# Motor_Control.net
KiCad netlist of a schematic drawn in Altium Designer
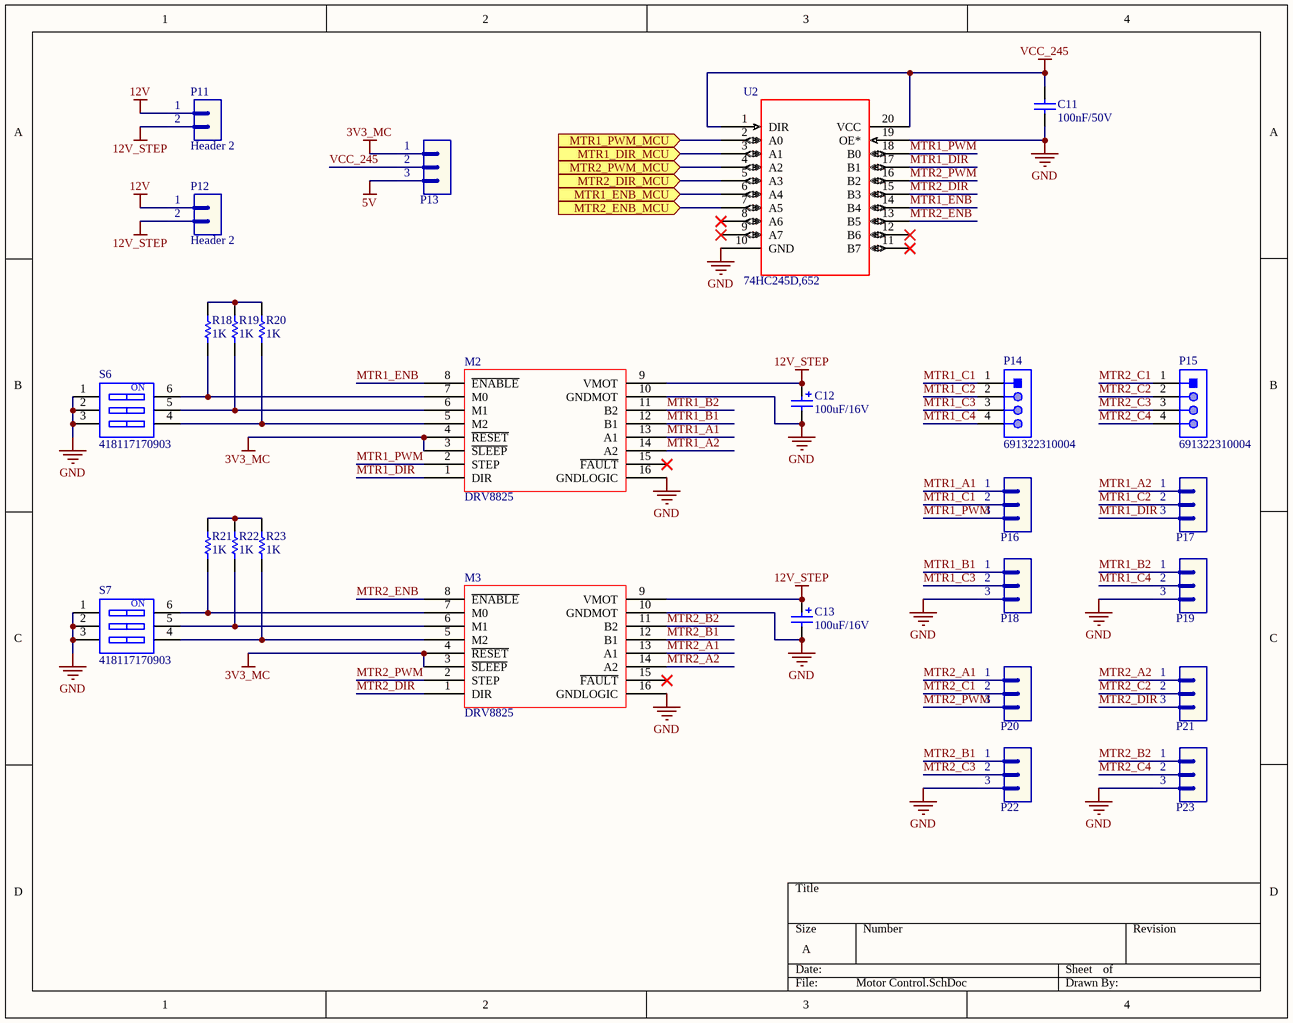
[diagram p0: Motor Control.SchDoc]

(export (version "E")
  (design (tool "Eeschema 10.0.6"))
  (components
    (comp (ref "C11")
      (value "100nF/50V")
      (footprint "CAP-SM-0805")
      (description "CAP CER 0.1UF 50V Y5V 0805")
      (fields
        (field (name "MANUFACTURER") "Samsung Electro-Mechanics")
        (field (name "MANUFACTURER PART NUMBER") "CL21F104ZBCNNNC")
      )
      (libsource (lib "Capacitor") (part "Cap-100nF-50V-0805"))
    )
    (comp (ref "C12")
      (value "100uF/16V")
      (footprint "CAP-SM-AL-SIZE-D-D6L6")
      (description "CAP ALUM 100UF 20% 16V SMD")
      (fields
        (field (name "MANUFACTURER") "Nichicon")
        (field (name "MANUFACTURER PART NUMBER") "UWX1C101MCL1GB")
      )
      (libsource (lib "Capacitor") (part "Cap-Al-100uF-16V-D6L5"))
    )
    (comp (ref "C13")
      (value "100uF/16V")
      (footprint "CAP-SM-AL-SIZE-D-D6L6")
      (description "CAP ALUM 100UF 20% 16V SMD")
      (fields
        (field (name "MANUFACTURER") "Nichicon")
        (field (name "MANUFACTURER PART NUMBER") "UWX1C101MCL1GB")
      )
      (libsource (lib "Capacitor") (part "Cap-Al-100uF-16V-D6L5"))
    )
    (comp (ref "M2") (value "DRV8825") (footprint "DRV8825") (libsource (lib "chicken") (part "DRV8825")))
    (comp (ref "M3") (value "DRV8825") (footprint "DRV8825") (libsource (lib "chicken") (part "DRV8825")))
    (comp (ref "P11")
      (value "Header 2")
      (footprint "JP2")
      (description "Header, 2-Pin")
      (fields (field (name "PUBLISHER") "Altium Limited"))
      (libsource (lib "Header-connector") (part "Header 2"))
    )
    (comp (ref "P12")
      (value "Header 2")
      (footprint "JP2")
      (description "Header, 2-Pin")
      (fields (field (name "PUBLISHER") "Altium Limited"))
      (libsource (lib "Header-connector") (part "Header 2"))
    )
    (comp (ref "P13")
      (value "Header 3")
      (footprint "JP3")
      (description "Header, 3-Pin")
      (fields (field (name "PUBLISHER") "Altium Limited"))
      (libsource (lib "Header-connector") (part "Header 3"))
    )
    (comp (ref "P14")
      (value "691322310004")
      (footprint "691322310004")
      (description "WR-TBL Serie 322 Horizontal PCB Header, Pluggable, pitch 3.81mm, 4p")
      (fields (field (name "PUBLISHER") "Wurth Elektronik"))
      (libsource (lib "o162719v243 Altium_WR-TBL (rev19a)") (part "691322310004"))
    )
    (comp (ref "P15")
      (value "691322310004")
      (footprint "691322310004")
      (description "WR-TBL Serie 322 Horizontal PCB Header, Pluggable, pitch 3.81mm, 4p")
      (fields (field (name "PUBLISHER") "Wurth Elektronik"))
      (libsource (lib "o162719v243 Altium_WR-TBL (rev19a)") (part "691322310004"))
    )
    (comp (ref "P16")
      (value "Header 3")
      (footprint "JP3")
      (description "Header, 3-Pin")
      (fields (field (name "PUBLISHER") "Altium Limited"))
      (libsource (lib "Header-connector") (part "Header 3"))
    )
    (comp (ref "P17")
      (value "Header 3")
      (footprint "JP3")
      (description "Header, 3-Pin")
      (fields (field (name "PUBLISHER") "Altium Limited"))
      (libsource (lib "Header-connector") (part "Header 3"))
    )
    (comp (ref "P18")
      (value "Header 3")
      (footprint "JP3")
      (description "Header, 3-Pin")
      (fields (field (name "PUBLISHER") "Altium Limited"))
      (libsource (lib "Header-connector") (part "Header 3"))
    )
    (comp (ref "P19")
      (value "Header 3")
      (footprint "JP3")
      (description "Header, 3-Pin")
      (fields (field (name "PUBLISHER") "Altium Limited"))
      (libsource (lib "Header-connector") (part "Header 3"))
    )
    (comp (ref "P20")
      (value "Header 3")
      (footprint "JP3")
      (description "Header, 3-Pin")
      (fields (field (name "PUBLISHER") "Altium Limited"))
      (libsource (lib "Header-connector") (part "Header 3"))
    )
    (comp (ref "P21")
      (value "Header 3")
      (footprint "JP3")
      (description "Header, 3-Pin")
      (fields (field (name "PUBLISHER") "Altium Limited"))
      (libsource (lib "Header-connector") (part "Header 3"))
    )
    (comp (ref "P22")
      (value "Header 3")
      (footprint "JP3")
      (description "Header, 3-Pin")
      (fields (field (name "PUBLISHER") "Altium Limited"))
      (libsource (lib "Header-connector") (part "Header 3"))
    )
    (comp (ref "P23")
      (value "Header 3")
      (footprint "JP3")
      (description "Header, 3-Pin")
      (fields (field (name "PUBLISHER") "Altium Limited"))
      (libsource (lib "Header-connector") (part "Header 3"))
    )
    (comp (ref "R18")
      (value "1K")
      (footprint "Resistor:RES-SM-0805")
      (description "RES 1K OHM 1% 1/4W 0805")
      (fields
        (field (name "MANUFACTURER") "Stackpole Electronics Inc")
        (field (name "MANUFACTURER PART NUMBER") "RNCP0805FTD1K00")
      )
      (libsource (lib "Resistor") (part "Res-1K-0805"))
    )
    (comp (ref "R19")
      (value "1K")
      (footprint "Resistor:RES-SM-0805")
      (description "RES 1K OHM 1% 1/4W 0805")
      (fields
        (field (name "MANUFACTURER") "Stackpole Electronics Inc")
        (field (name "MANUFACTURER PART NUMBER") "RNCP0805FTD1K00")
      )
      (libsource (lib "Resistor") (part "Res-1K-0805"))
    )
    (comp (ref "R20")
      (value "1K")
      (footprint "Resistor:RES-SM-0805")
      (description "RES 1K OHM 1% 1/4W 0805")
      (fields
        (field (name "MANUFACTURER") "Stackpole Electronics Inc")
        (field (name "MANUFACTURER PART NUMBER") "RNCP0805FTD1K00")
      )
      (libsource (lib "Resistor") (part "Res-1K-0805"))
    )
    (comp (ref "R21")
      (value "1K")
      (footprint "Resistor:RES-SM-0805")
      (description "RES 1K OHM 1% 1/4W 0805")
      (fields
        (field (name "MANUFACTURER") "Stackpole Electronics Inc")
        (field (name "MANUFACTURER PART NUMBER") "RNCP0805FTD1K00")
      )
      (libsource (lib "Resistor") (part "Res-1K-0805"))
    )
    (comp (ref "R22")
      (value "1K")
      (footprint "Resistor:RES-SM-0805")
      (description "RES 1K OHM 1% 1/4W 0805")
      (fields
        (field (name "MANUFACTURER") "Stackpole Electronics Inc")
        (field (name "MANUFACTURER PART NUMBER") "RNCP0805FTD1K00")
      )
      (libsource (lib "Resistor") (part "Res-1K-0805"))
    )
    (comp (ref "R23")
      (value "1K")
      (footprint "Resistor:RES-SM-0805")
      (description "RES 1K OHM 1% 1/4W 0805")
      (fields
        (field (name "MANUFACTURER") "Stackpole Electronics Inc")
        (field (name "MANUFACTURER PART NUMBER") "RNCP0805FTD1K00")
      )
      (libsource (lib "Resistor") (part "Res-1K-0805"))
    )
    (comp (ref "S6")
      (value "418117170903")
      (footprint "418117170903")
      (description "WS-DITV Compact THT Dip Switch, Flat Actuator, pitch 2.54mm, 3p")
      (fields (field (name "PUBLISHER") "Wurth Elektronik"))
      (libsource (lib "418117170903_Altium_WS-DITV_rev19a") (part "418117170903"))
    )
    (comp (ref "S7")
      (value "418117170903")
      (footprint "418117170903")
      (description "WS-DITV Compact THT Dip Switch, Flat Actuator, pitch 2.54mm, 3p")
      (fields (field (name "PUBLISHER") "Wurth Elektronik"))
      (libsource (lib "418117170903_Altium_WS-DITV_rev19a") (part "418117170903"))
    )
    (comp (ref "U2")
      (value "74HC245D,652")
      (footprint "74HC245D,652")
      (description "No Description Available")
      (fields (field (name "COPYRIGHT") "Copyright (C) 2016 Accelerated Designs. All rights reserved"))
      (libsource (lib "chicken") (part "74HC245D,652"))
    )
  )
  (nets
    (net (code "1") (name "/MTR1_A1") (class "Default")
      (node (ref "M2") (pin "13") (pinfunction "A1_13") (pintype "passive"))
      (node (ref "P16") (pin "1") (pinfunction "1_1") (pintype "passive"))
    )
    (net (code "2") (name "/MTR1_A2") (class "Default")
      (node (ref "M2") (pin "14") (pinfunction "A2_14") (pintype "passive"))
      (node (ref "P17") (pin "1") (pinfunction "1_1") (pintype "passive"))
    )
    (net (code "3") (name "/MTR1_B1") (class "Default")
      (node (ref "M2") (pin "12") (pinfunction "B1_12") (pintype "passive"))
      (node (ref "P18") (pin "1") (pinfunction "1_1") (pintype "passive"))
    )
    (net (code "4") (name "/MTR1_B2") (class "Default")
      (node (ref "M2") (pin "11") (pinfunction "B2_11") (pintype "passive"))
      (node (ref "P19") (pin "1") (pinfunction "1_1") (pintype "passive"))
    )
    (net (code "5") (name "/MTR1_C1") (class "Default")
      (node (ref "P14") (pin "1") (pinfunction "1_1") (pintype "passive"))
      (node (ref "P16") (pin "2") (pinfunction "2_2") (pintype "passive"))
    )
    (net (code "6") (name "/MTR1_C2") (class "Default")
      (node (ref "P14") (pin "2") (pinfunction "2_2") (pintype "passive"))
      (node (ref "P17") (pin "2") (pinfunction "2_2") (pintype "passive"))
    )
    (net (code "7") (name "/MTR1_C3") (class "Default")
      (node (ref "P14") (pin "3") (pinfunction "3_3") (pintype "passive"))
      (node (ref "P18") (pin "2") (pinfunction "2_2") (pintype "passive"))
    )
    (net (code "8") (name "/MTR1_C4") (class "Default")
      (node (ref "P14") (pin "4") (pinfunction "4_4") (pintype "passive"))
      (node (ref "P19") (pin "2") (pinfunction "2_2") (pintype "passive"))
    )
    (net (code "9") (name "/MTR1_DIR") (class "Default")
      (node (ref "M2") (pin "1") (pinfunction "DIR_1") (pintype "passive"))
      (node (ref "P17") (pin "3") (pinfunction "3_3") (pintype "passive"))
      (node (ref "U2") (pin "17") (pinfunction "B1_17") (pintype "bidirectional"))
    )
    (net (code "10") (name "/MTR1_DIR_MCU") (class "Default")
      (node (ref "U2") (pin "3") (pinfunction "A1_3") (pintype "bidirectional"))
    )
    (net (code "11") (name "/MTR1_ENB") (class "Default")
      (node (ref "M2") (pin "8") (pinfunction "~{ENABLE}_8") (pintype "passive"))
      (node (ref "U2") (pin "14") (pinfunction "B4_14") (pintype "bidirectional"))
    )
    (net (code "12") (name "/MTR1_ENB_MCU") (class "Default")
      (node (ref "U2") (pin "6") (pinfunction "A4_6") (pintype "bidirectional"))
    )
    (net (code "13") (name "/MTR1_PWM") (class "Default")
      (node (ref "M2") (pin "2") (pinfunction "STEP_2") (pintype "passive"))
      (node (ref "P16") (pin "3") (pinfunction "3_3") (pintype "passive"))
      (node (ref "U2") (pin "18") (pinfunction "B0_18") (pintype "bidirectional"))
    )
    (net (code "14") (name "/MTR1_PWM_MCU") (class "Default")
      (node (ref "U2") (pin "2") (pinfunction "A0_2") (pintype "bidirectional"))
    )
    (net (code "15") (name "/MTR2_A1") (class "Default")
      (node (ref "M3") (pin "13") (pinfunction "A1_13") (pintype "passive"))
      (node (ref "P20") (pin "1") (pinfunction "1_1") (pintype "passive"))
    )
    (net (code "16") (name "/MTR2_A2") (class "Default")
      (node (ref "M3") (pin "14") (pinfunction "A2_14") (pintype "passive"))
      (node (ref "P21") (pin "1") (pinfunction "1_1") (pintype "passive"))
    )
    (net (code "17") (name "/MTR2_B1") (class "Default")
      (node (ref "M3") (pin "12") (pinfunction "B1_12") (pintype "passive"))
      (node (ref "P22") (pin "1") (pinfunction "1_1") (pintype "passive"))
    )
    (net (code "18") (name "/MTR2_B2") (class "Default")
      (node (ref "M3") (pin "11") (pinfunction "B2_11") (pintype "passive"))
      (node (ref "P23") (pin "1") (pinfunction "1_1") (pintype "passive"))
    )
    (net (code "19") (name "/MTR2_C1") (class "Default")
      (node (ref "P15") (pin "1") (pinfunction "1_1") (pintype "passive"))
      (node (ref "P20") (pin "2") (pinfunction "2_2") (pintype "passive"))
    )
    (net (code "20") (name "/MTR2_C2") (class "Default")
      (node (ref "P15") (pin "2") (pinfunction "2_2") (pintype "passive"))
      (node (ref "P21") (pin "2") (pinfunction "2_2") (pintype "passive"))
    )
    (net (code "21") (name "/MTR2_C3") (class "Default")
      (node (ref "P15") (pin "3") (pinfunction "3_3") (pintype "passive"))
      (node (ref "P22") (pin "2") (pinfunction "2_2") (pintype "passive"))
    )
    (net (code "22") (name "/MTR2_C4") (class "Default")
      (node (ref "P15") (pin "4") (pinfunction "4_4") (pintype "passive"))
      (node (ref "P23") (pin "2") (pinfunction "2_2") (pintype "passive"))
    )
    (net (code "23") (name "/MTR2_DIR") (class "Default")
      (node (ref "M3") (pin "1") (pinfunction "DIR_1") (pintype "passive"))
      (node (ref "P21") (pin "3") (pinfunction "3_3") (pintype "passive"))
      (node (ref "U2") (pin "15") (pinfunction "B3_15") (pintype "bidirectional"))
    )
    (net (code "24") (name "/MTR2_DIR_MCU") (class "Default")
      (node (ref "U2") (pin "5") (pinfunction "A3_5") (pintype "bidirectional"))
    )
    (net (code "25") (name "/MTR2_ENB") (class "Default")
      (node (ref "M3") (pin "8") (pinfunction "~{ENABLE}_8") (pintype "passive"))
      (node (ref "U2") (pin "13") (pinfunction "B5_13") (pintype "bidirectional"))
    )
    (net (code "26") (name "/MTR2_ENB_MCU") (class "Default")
      (node (ref "U2") (pin "7") (pinfunction "A5_7") (pintype "bidirectional"))
    )
    (net (code "27") (name "/MTR2_PWM") (class "Default")
      (node (ref "M3") (pin "2") (pinfunction "STEP_2") (pintype "passive"))
      (node (ref "P20") (pin "3") (pinfunction "3_3") (pintype "passive"))
      (node (ref "U2") (pin "16") (pinfunction "B2_16") (pintype "bidirectional"))
    )
    (net (code "28") (name "/MTR2_PWM_MCU") (class "Default")
      (node (ref "U2") (pin "4") (pinfunction "A2_4") (pintype "bidirectional"))
    )
    (net (code "29") (name "3V3_MC") (class "Default")
      (node (ref "M2") (pin "3") (pinfunction "~{SLEEP}_3") (pintype "passive"))
      (node (ref "M2") (pin "4") (pinfunction "~{RESET}_4") (pintype "passive"))
      (node (ref "M3") (pin "3") (pinfunction "~{SLEEP}_3") (pintype "passive"))
      (node (ref "M3") (pin "4") (pinfunction "~{RESET}_4") (pintype "passive"))
      (node (ref "P13") (pin "1") (pinfunction "1_1") (pintype "passive"))
    )
    (net (code "30") (name "5V") (class "Default")
      (node (ref "P13") (pin "3") (pinfunction "3_3") (pintype "passive"))
    )
    (net (code "31") (name "12V") (class "Default")
      (node (ref "P11") (pin "1") (pinfunction "1_1") (pintype "passive"))
      (node (ref "P12") (pin "1") (pinfunction "1_1") (pintype "passive"))
    )
    (net (code "32") (name "12V_STEP") (class "Default")
      (node (ref "C12") (pin "1") (pinfunction "1_1") (pintype "passive"))
      (node (ref "C13") (pin "1") (pinfunction "1_1") (pintype "passive"))
      (node (ref "M2") (pin "9") (pinfunction "VMOT_9") (pintype "passive"))
      (node (ref "M3") (pin "9") (pinfunction "VMOT_9") (pintype "passive"))
      (node (ref "P11") (pin "2") (pinfunction "2_2") (pintype "passive"))
      (node (ref "P12") (pin "2") (pinfunction "2_2") (pintype "passive"))
    )
    (net (code "33") (name "GND") (class "Default")
      (node (ref "C11") (pin "1") (pinfunction "1_1") (pintype "passive"))
      (node (ref "C12") (pin "2") (pinfunction "2_2") (pintype "passive"))
      (node (ref "C13") (pin "2") (pinfunction "2_2") (pintype "passive"))
      (node (ref "M2") (pin "10") (pinfunction "GNDMOT_10") (pintype "passive"))
      (node (ref "M2") (pin "16") (pinfunction "GNDLOGIC_16") (pintype "passive"))
      (node (ref "M3") (pin "10") (pinfunction "GNDMOT_10") (pintype "passive"))
      (node (ref "M3") (pin "16") (pinfunction "GNDLOGIC_16") (pintype "passive"))
      (node (ref "P18") (pin "3") (pinfunction "3_3") (pintype "passive"))
      (node (ref "P19") (pin "3") (pinfunction "3_3") (pintype "passive"))
      (node (ref "P22") (pin "3") (pinfunction "3_3") (pintype "passive"))
      (node (ref "P23") (pin "3") (pinfunction "3_3") (pintype "passive"))
      (node (ref "S6") (pin "1") (pinfunction "1_1") (pintype "passive"))
      (node (ref "S6") (pin "2") (pinfunction "2_2") (pintype "passive"))
      (node (ref "S6") (pin "3") (pinfunction "3_3") (pintype "passive"))
      (node (ref "S7") (pin "1") (pinfunction "1_1") (pintype "passive"))
      (node (ref "S7") (pin "2") (pinfunction "2_2") (pintype "passive"))
      (node (ref "S7") (pin "3") (pinfunction "3_3") (pintype "passive"))
      (node (ref "U2") (pin "10") (pinfunction "GND_10") (pintype "power_in"))
      (node (ref "U2") (pin "19") (pinfunction "OE*_19") (pintype "input"))
    )
    (net (code "34") (name "Net-(M2-M0)") (class "Default")
      (node (ref "M2") (pin "7") (pinfunction "M0_7") (pintype "passive"))
      (node (ref "R18") (pin "1") (pinfunction "1_1") (pintype "passive"))
      (node (ref "S6") (pin "6") (pinfunction "6_6") (pintype "passive"))
    )
    (net (code "35") (name "Net-(M2-M1)") (class "Default")
      (node (ref "M2") (pin "6") (pinfunction "M1_6") (pintype "passive"))
      (node (ref "R19") (pin "1") (pinfunction "1_1") (pintype "passive"))
      (node (ref "S6") (pin "5") (pinfunction "5_5") (pintype "passive"))
    )
    (net (code "36") (name "Net-(M2-M2)") (class "Default")
      (node (ref "M2") (pin "5") (pinfunction "M2_5") (pintype "passive"))
      (node (ref "R20") (pin "1") (pinfunction "1_1") (pintype "passive"))
      (node (ref "S6") (pin "4") (pinfunction "4_4") (pintype "passive"))
    )
    (net (code "37") (name "Net-(M3-M0)") (class "Default")
      (node (ref "M3") (pin "7") (pinfunction "M0_7") (pintype "passive"))
      (node (ref "R21") (pin "1") (pinfunction "1_1") (pintype "passive"))
      (node (ref "S7") (pin "6") (pinfunction "6_6") (pintype "passive"))
    )
    (net (code "38") (name "Net-(M3-M1)") (class "Default")
      (node (ref "M3") (pin "6") (pinfunction "M1_6") (pintype "passive"))
      (node (ref "R22") (pin "1") (pinfunction "1_1") (pintype "passive"))
      (node (ref "S7") (pin "5") (pinfunction "5_5") (pintype "passive"))
    )
    (net (code "39") (name "Net-(M3-M2)") (class "Default")
      (node (ref "M3") (pin "5") (pinfunction "M2_5") (pintype "passive"))
      (node (ref "R23") (pin "1") (pinfunction "1_1") (pintype "passive"))
      (node (ref "S7") (pin "4") (pinfunction "4_4") (pintype "passive"))
    )
    (net (code "40") (name "Net-(R18-Pad2)") (class "Default")
      (node (ref "R18") (pin "2") (pinfunction "2_2") (pintype "passive"))
      (node (ref "R19") (pin "2") (pinfunction "2_2") (pintype "passive"))
      (node (ref "R20") (pin "2") (pinfunction "2_2") (pintype "passive"))
    )
    (net (code "41") (name "Net-(R21-Pad2)") (class "Default")
      (node (ref "R21") (pin "2") (pinfunction "2_2") (pintype "passive"))
      (node (ref "R22") (pin "2") (pinfunction "2_2") (pintype "passive"))
      (node (ref "R23") (pin "2") (pinfunction "2_2") (pintype "passive"))
    )
    (net (code "42") (name "VCC_245") (class "Default")
      (node (ref "C11") (pin "2") (pinfunction "2_2") (pintype "passive"))
      (node (ref "P13") (pin "2") (pinfunction "2_2") (pintype "passive"))
      (node (ref "U2") (pin "1") (pinfunction "DIR_1") (pintype "input"))
      (node (ref "U2") (pin "20") (pinfunction "VCC_20") (pintype "power_in"))
    )
    (net (code "43") (name "unconnected-(M2-~{FAULT}-Pad15)") (class "Default")
      (node (ref "M2") (pin "15") (pinfunction "~{FAULT}_15") (pintype "passive+no_connect"))
    )
    (net (code "44") (name "unconnected-(M3-~{FAULT}-Pad15)") (class "Default")
      (node (ref "M3") (pin "15") (pinfunction "~{FAULT}_15") (pintype "passive+no_connect"))
    )
    (net (code "45") (name "unconnected-(U2-A6-Pad8)") (class "Default")
      (node (ref "U2") (pin "8") (pinfunction "A6_8") (pintype "bidirectional+no_connect"))
    )
    (net (code "46") (name "unconnected-(U2-A7-Pad9)") (class "Default")
      (node (ref "U2") (pin "9") (pinfunction "A7_9") (pintype "bidirectional+no_connect"))
    )
    (net (code "47") (name "unconnected-(U2-B6-Pad12)") (class "Default")
      (node (ref "U2") (pin "12") (pinfunction "B6_12") (pintype "bidirectional+no_connect"))
    )
    (net (code "48") (name "unconnected-(U2-B7-Pad11)") (class "Default")
      (node (ref "U2") (pin "11") (pinfunction "B7_11") (pintype "bidirectional+no_connect"))
    )
  )
)
